# LED_Driver.net
KiCad netlist of a schematic drawn in Altium Designer
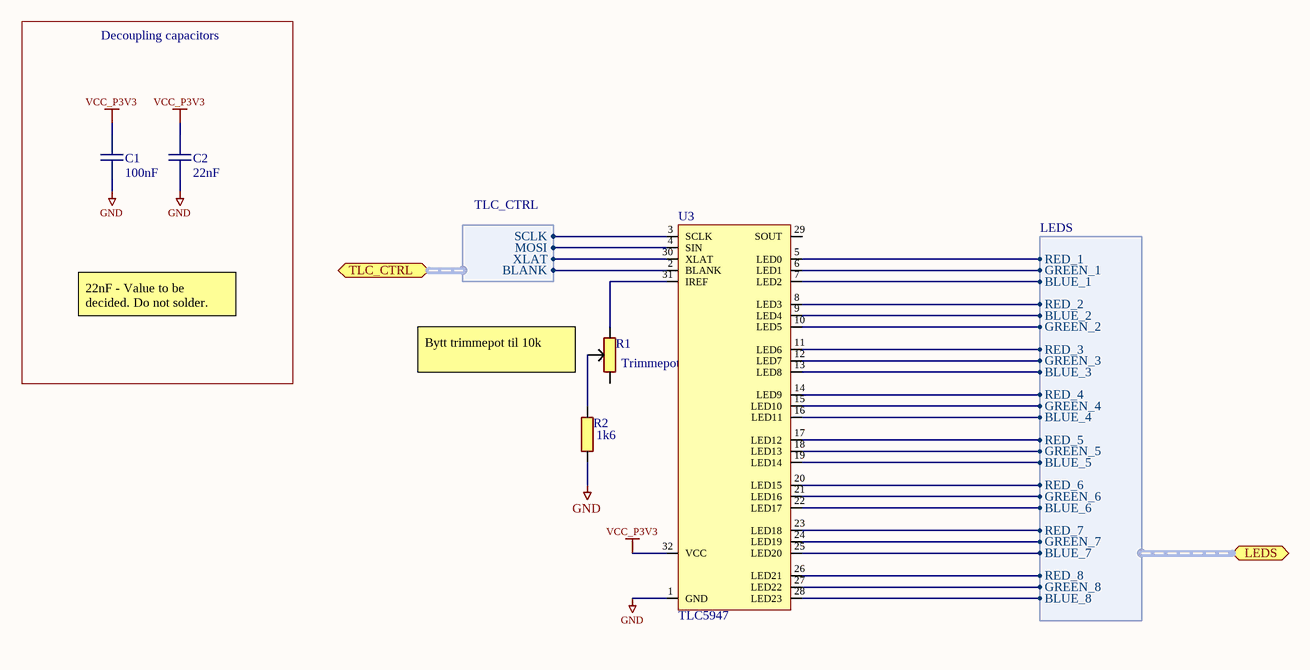
[diagram p0: LED Driver.SchDoc]

(export (version "E")
  (design (tool "Eeschema 10.0.6"))
  (components
    (comp (ref "C1")
      (value "100nF")
      (footprint "CAPC0603(1608)55_N")
      (description "X7R 50V 5%")
      (libsource (lib "OVLib") (part "CAP"))
    )
    (comp (ref "C2")
      (value "22nF")
      (footprint "CAPC0805(2012)100_N")
      (description "X7R 50V")
      (libsource (lib "OVLib") (part "CAP"))
    )
    (comp (ref "R1")
      (value "Trimmepot 500ohm")
      (footprint "TRIMPOT_3006P")
      (description "15 turn, horizontal")
      (libsource (lib "OVLib") (part "Potmeter"))
    )
    (comp (ref "R2")
      (value "1k6")
      (footprint "RESC0603(1608)_N")
      (description "0.1W 1% Thick film resistor")
      (libsource (lib "OVLib") (part "Resistor2"))
    )
    (comp (ref "U3") (value "TLC5947") (libsource (lib "Schlib1") (part "TLC5947")))
  )
  (nets
    (net (code "3") (name "/BLANK") (class "Default")
      (node (ref "U3") (pin "2") (pinfunction "BLANK_2") (pintype "passive"))
    )
    (net (code "4") (name "/BLUE_1") (class "Default")
      (node (ref "U3") (pin "7") (pinfunction "LED2_7") (pintype "passive"))
    )
    (net (code "5") (name "/BLUE_2") (class "Default")
      (node (ref "U3") (pin "9") (pinfunction "LED4_9") (pintype "passive"))
    )
    (net (code "6") (name "/BLUE_3") (class "Default")
      (node (ref "U3") (pin "13") (pinfunction "LED8_13") (pintype "passive"))
    )
    (net (code "7") (name "/BLUE_4") (class "Default")
      (node (ref "U3") (pin "16") (pinfunction "LED11_16") (pintype "passive"))
    )
    (net (code "8") (name "/BLUE_5") (class "Default")
      (node (ref "U3") (pin "19") (pinfunction "LED14_19") (pintype "passive"))
    )
    (net (code "9") (name "/BLUE_6") (class "Default")
      (node (ref "U3") (pin "22") (pinfunction "LED17_22") (pintype "passive"))
    )
    (net (code "10") (name "/BLUE_7") (class "Default")
      (node (ref "U3") (pin "25") (pinfunction "LED20_25") (pintype "passive"))
    )
    (net (code "11") (name "/BLUE_8") (class "Default")
      (node (ref "U3") (pin "28") (pinfunction "LED23_28") (pintype "passive"))
    )
    (net (code "12") (name "/GREEN_1") (class "Default")
      (node (ref "U3") (pin "6") (pinfunction "LED1_6") (pintype "passive"))
    )
    (net (code "13") (name "/GREEN_2") (class "Default")
      (node (ref "U3") (pin "10") (pinfunction "LED5_10") (pintype "passive"))
    )
    (net (code "14") (name "/GREEN_3") (class "Default")
      (node (ref "U3") (pin "12") (pinfunction "LED7_12") (pintype "passive"))
    )
    (net (code "15") (name "/GREEN_4") (class "Default")
      (node (ref "U3") (pin "15") (pinfunction "LED10_15") (pintype "passive"))
    )
    (net (code "16") (name "/GREEN_5") (class "Default")
      (node (ref "U3") (pin "18") (pinfunction "LED13_18") (pintype "passive"))
    )
    (net (code "17") (name "/GREEN_6") (class "Default")
      (node (ref "U3") (pin "21") (pinfunction "LED16_21") (pintype "passive"))
    )
    (net (code "18") (name "/GREEN_7") (class "Default")
      (node (ref "U3") (pin "24") (pinfunction "LED19_24") (pintype "passive"))
    )
    (net (code "19") (name "/GREEN_8") (class "Default")
      (node (ref "U3") (pin "27") (pinfunction "LED22_27") (pintype "passive"))
    )
    (net (code "20") (name "/MOSI") (class "Default")
      (node (ref "U3") (pin "4") (pinfunction "SIN_4") (pintype "passive"))
    )
    (net (code "21") (name "/RED_1") (class "Default")
      (node (ref "U3") (pin "5") (pinfunction "LED0_5") (pintype "passive"))
    )
    (net (code "22") (name "/RED_2") (class "Default")
      (node (ref "U3") (pin "8") (pinfunction "LED3_8") (pintype "passive"))
    )
    (net (code "23") (name "/RED_3") (class "Default")
      (node (ref "U3") (pin "11") (pinfunction "LED6_11") (pintype "passive"))
    )
    (net (code "24") (name "/RED_4") (class "Default")
      (node (ref "U3") (pin "14") (pinfunction "LED9_14") (pintype "passive"))
    )
    (net (code "25") (name "/RED_5") (class "Default")
      (node (ref "U3") (pin "17") (pinfunction "LED12_17") (pintype "passive"))
    )
    (net (code "26") (name "/RED_6") (class "Default")
      (node (ref "U3") (pin "20") (pinfunction "LED15_20") (pintype "passive"))
    )
    (net (code "27") (name "/RED_7") (class "Default")
      (node (ref "U3") (pin "23") (pinfunction "LED18_23") (pintype "passive"))
    )
    (net (code "28") (name "/RED_8") (class "Default")
      (node (ref "U3") (pin "26") (pinfunction "LED21_26") (pintype "passive"))
    )
    (net (code "29") (name "/SCLK") (class "Default")
      (node (ref "U3") (pin "3") (pinfunction "SCLK_3") (pintype "passive"))
    )
    (net (code "30") (name "/XLAT") (class "Default")
      (node (ref "U3") (pin "30") (pinfunction "XLAT_30") (pintype "passive"))
    )
    (net (code "33") (name "GND") (class "Default")
      (node (ref "C1") (pin "1") (pinfunction "1_1") (pintype "passive"))
      (node (ref "C2") (pin "1") (pinfunction "1_1") (pintype "passive"))
      (node (ref "R2") (pin "1") (pinfunction "1_1") (pintype "passive"))
      (node (ref "U3") (pin "1") (pinfunction "GND_1") (pintype "passive"))
    )
    (net (code "34") (name "Net-(R1-Pad2)") (class "Default")
      (node (ref "R1") (pin "2") (pinfunction "2_2") (pintype "passive"))
      (node (ref "R2") (pin "2") (pinfunction "2_2") (pintype "passive"))
    )
    (net (code "35") (name "Net-(U3-IREF)") (class "Default")
      (node (ref "R1") (pin "3") (pinfunction "3_3") (pintype "passive"))
      (node (ref "U3") (pin "31") (pinfunction "IREF_31") (pintype "passive"))
    )
    (net (code "36") (name "VCC_P3V3") (class "Default")
      (node (ref "C1") (pin "2") (pinfunction "2_2") (pintype "passive"))
      (node (ref "C2") (pin "2") (pinfunction "2_2") (pintype "passive"))
      (node (ref "U3") (pin "32") (pinfunction "VCC_32") (pintype "passive"))
    )
    (net (code "37") (name "unconnected-(R1-Pad1)") (class "Default")
      (node (ref "R1") (pin "1") (pinfunction "1_1") (pintype "passive"))
    )
    (net (code "38") (name "unconnected-(U3-SOUT-Pad29)") (class "Default")
      (node (ref "U3") (pin "29") (pinfunction "SOUT_29") (pintype "passive"))
    )
  )
)
